# EntradaDigital.net
KiCad netlist of a schematic drawn in Altium Designer
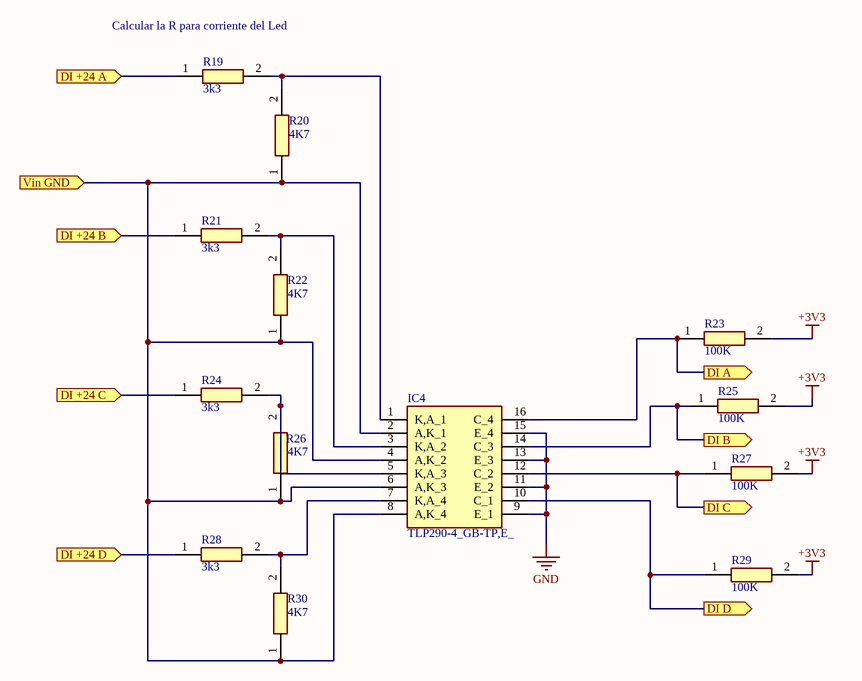
[diagram p0: EntradaDigital.SchDoc]

(export (version "E")
  (design (tool "Eeschema 10.0.6"))
  (components
    (comp (ref "IC4")
      (value "TLP290-4_GB-TP,E_")
      (footprint "SamacSys:SOIC127P700X230-16N")
      (description "Integrated Circuit")
      (fields
        (field (name "MANUFACTURER_PART_NUMBER") "TLP290-4(GB-TP,E)")
        (field (name "MOUSER PART NUMBER") "757-TLP2904GBTPE")
      )
      (libsource (lib "*") (part "TLP290-4_GB-TP,E_"))
    )
    (comp (ref "R19")
      (value "3k3")
      (footprint "SamacSys:RESC3216X75N")
      (description "Resistor")
      (fields
        (field (name "MANUFACTURER_PART_NUMBER") "CR1206-F/-2R00ELF")
        (field (name "MOUSER PART NUMBER") "652-CR1206-F/2R00ELF")
      )
      (libsource (lib "*") (part "CR1206-F_-2R00ELF"))
    )
    (comp (ref "R20")
      (value "4K7")
      (footprint "SamacSys:RESC3216X75N")
      (description "Resistor")
      (fields
        (field (name "MANUFACTURER_PART_NUMBER") "CR1206-F/-2R00ELF")
        (field (name "MOUSER PART NUMBER") "652-CR1206-F/2R00ELF")
      )
      (libsource (lib "") (part "CR1206-F_-2R00ELF_1"))
    )
    (comp (ref "R21")
      (value "3k3")
      (footprint "SamacSys:RESC3216X75N")
      (description "Resistor")
      (fields
        (field (name "MANUFACTURER_PART_NUMBER") "CR1206-F/-2R00ELF")
        (field (name "MOUSER PART NUMBER") "652-CR1206-F/2R00ELF")
      )
      (libsource (lib "*") (part "CR1206-F_-2R00ELF"))
    )
    (comp (ref "R22")
      (value "4K7")
      (footprint "SamacSys:RESC3216X75N")
      (description "Resistor")
      (fields
        (field (name "MANUFACTURER_PART_NUMBER") "CR1206-F/-2R00ELF")
        (field (name "MOUSER PART NUMBER") "652-CR1206-F/2R00ELF")
      )
      (libsource (lib "") (part "CR1206-F_-2R00ELF_1"))
    )
    (comp (ref "R23")
      (value "100K")
      (footprint "SamacSys:RESC3216X75N")
      (description "Resistor")
      (fields
        (field (name "MANUFACTURER_PART_NUMBER") "CR1206-F/-2R00ELF")
        (field (name "MOUSER PART NUMBER") "652-CR1206-F/2R00ELF")
      )
      (libsource (lib "*") (part "CR1206-F_-2R00ELF"))
    )
    (comp (ref "R24")
      (value "3k3")
      (footprint "SamacSys:RESC3216X75N")
      (description "Resistor")
      (fields
        (field (name "MANUFACTURER_PART_NUMBER") "CR1206-F/-2R00ELF")
        (field (name "MOUSER PART NUMBER") "652-CR1206-F/2R00ELF")
      )
      (libsource (lib "*") (part "CR1206-F_-2R00ELF"))
    )
    (comp (ref "R25")
      (value "100K")
      (footprint "SamacSys:RESC3216X75N")
      (description "Resistor")
      (fields
        (field (name "MANUFACTURER_PART_NUMBER") "CR1206-F/-2R00ELF")
        (field (name "MOUSER PART NUMBER") "652-CR1206-F/2R00ELF")
      )
      (libsource (lib "*") (part "CR1206-F_-2R00ELF"))
    )
    (comp (ref "R26")
      (value "4K7")
      (footprint "SamacSys:RESC3216X75N")
      (description "Resistor")
      (fields
        (field (name "MANUFACTURER_PART_NUMBER") "CR1206-F/-2R00ELF")
        (field (name "MOUSER PART NUMBER") "652-CR1206-F/2R00ELF")
      )
      (libsource (lib "") (part "CR1206-F_-2R00ELF_1"))
    )
    (comp (ref "R27")
      (value "100K")
      (footprint "SamacSys:RESC3216X75N")
      (description "Resistor")
      (fields
        (field (name "MANUFACTURER_PART_NUMBER") "CR1206-F/-2R00ELF")
        (field (name "MOUSER PART NUMBER") "652-CR1206-F/2R00ELF")
      )
      (libsource (lib "*") (part "CR1206-F_-2R00ELF"))
    )
    (comp (ref "R28")
      (value "3k3")
      (footprint "SamacSys:RESC3216X75N")
      (description "Resistor")
      (fields
        (field (name "MANUFACTURER_PART_NUMBER") "CR1206-F/-2R00ELF")
        (field (name "MOUSER PART NUMBER") "652-CR1206-F/2R00ELF")
      )
      (libsource (lib "*") (part "CR1206-F_-2R00ELF"))
    )
    (comp (ref "R29")
      (value "100K")
      (footprint "SamacSys:RESC3216X75N")
      (description "Resistor")
      (fields
        (field (name "MANUFACTURER_PART_NUMBER") "CR1206-F/-2R00ELF")
        (field (name "MOUSER PART NUMBER") "652-CR1206-F/2R00ELF")
      )
      (libsource (lib "*") (part "CR1206-F_-2R00ELF"))
    )
    (comp (ref "R30")
      (value "4K7")
      (footprint "SamacSys:RESC3216X75N")
      (description "Resistor")
      (fields
        (field (name "MANUFACTURER_PART_NUMBER") "CR1206-F/-2R00ELF")
        (field (name "MOUSER PART NUMBER") "652-CR1206-F/2R00ELF")
      )
      (libsource (lib "") (part "CR1206-F_-2R00ELF_1"))
    )
  )
  (nets
    (net (code "1") (name "+3V3") (class "Default")
      (node (ref "R23") (pin "2") (pinfunction "2_2") (pintype "passive"))
      (node (ref "R25") (pin "2") (pinfunction "2_2") (pintype "passive"))
      (node (ref "R27") (pin "2") (pinfunction "2_2") (pintype "passive"))
      (node (ref "R29") (pin "2") (pinfunction "2_2") (pintype "passive"))
    )
    (net (code "2") (name "/DI +24 A") (class "Default")
      (node (ref "R19") (pin "1") (pinfunction "1_1") (pintype "passive"))
    )
    (net (code "3") (name "/DI +24 B") (class "Default")
      (node (ref "R21") (pin "1") (pinfunction "1_1") (pintype "passive"))
    )
    (net (code "4") (name "/DI +24 C") (class "Default")
      (node (ref "R24") (pin "1") (pinfunction "1_1") (pintype "passive"))
    )
    (net (code "5") (name "/DI +24 D") (class "Default")
      (node (ref "R28") (pin "1") (pinfunction "1_1") (pintype "passive"))
    )
    (net (code "6") (name "/DI A") (class "Default")
      (node (ref "IC4") (pin "16") (pinfunction "C_4_16") (pintype "passive"))
      (node (ref "R23") (pin "1") (pinfunction "1_1") (pintype "passive"))
    )
    (net (code "7") (name "/DI B") (class "Default")
      (node (ref "IC4") (pin "14") (pinfunction "C_3_14") (pintype "passive"))
      (node (ref "R25") (pin "1") (pinfunction "1_1") (pintype "passive"))
    )
    (net (code "8") (name "/DI C") (class "Default")
      (node (ref "IC4") (pin "12") (pinfunction "C_2_12") (pintype "passive"))
      (node (ref "R27") (pin "1") (pinfunction "1_1") (pintype "passive"))
    )
    (net (code "9") (name "/DI D") (class "Default")
      (node (ref "IC4") (pin "10") (pinfunction "C_1_10") (pintype "passive"))
      (node (ref "R29") (pin "1") (pinfunction "1_1") (pintype "passive"))
    )
    (net (code "10") (name "/Vin GND") (class "Default")
      (node (ref "IC4") (pin "2") (pinfunction "A,K_1_2") (pintype "passive"))
      (node (ref "IC4") (pin "4") (pinfunction "A,K_2_4") (pintype "passive"))
      (node (ref "IC4") (pin "6") (pinfunction "A,K_3_6") (pintype "passive"))
      (node (ref "IC4") (pin "8") (pinfunction "A,K_4_8") (pintype "passive"))
      (node (ref "R20") (pin "1") (pinfunction "1_1") (pintype "passive"))
      (node (ref "R22") (pin "1") (pinfunction "1_1") (pintype "passive"))
      (node (ref "R26") (pin "1") (pinfunction "1_1") (pintype "passive"))
      (node (ref "R30") (pin "1") (pinfunction "1_1") (pintype "passive"))
    )
    (net (code "11") (name "GND") (class "Default")
      (node (ref "IC4") (pin "11") (pinfunction "E_2_11") (pintype "passive"))
      (node (ref "IC4") (pin "13") (pinfunction "E_3_13") (pintype "passive"))
      (node (ref "IC4") (pin "15") (pinfunction "E_4_15") (pintype "passive"))
      (node (ref "IC4") (pin "9") (pinfunction "E_1_9") (pintype "passive"))
    )
    (net (code "12") (name "Net-(IC4-K,A_1)") (class "Default")
      (node (ref "IC4") (pin "1") (pinfunction "K,A_1_1") (pintype "passive"))
      (node (ref "R19") (pin "2") (pinfunction "2_2") (pintype "passive"))
      (node (ref "R20") (pin "2") (pinfunction "2_2") (pintype "passive"))
    )
    (net (code "13") (name "Net-(IC4-K,A_2)") (class "Default")
      (node (ref "IC4") (pin "3") (pinfunction "K,A_2_3") (pintype "passive"))
      (node (ref "R21") (pin "2") (pinfunction "2_2") (pintype "passive"))
      (node (ref "R22") (pin "2") (pinfunction "2_2") (pintype "passive"))
    )
    (net (code "14") (name "Net-(IC4-K,A_3)") (class "Default")
      (node (ref "IC4") (pin "5") (pinfunction "K,A_3_5") (pintype "passive"))
      (node (ref "R24") (pin "2") (pinfunction "2_2") (pintype "passive"))
      (node (ref "R26") (pin "2") (pinfunction "2_2") (pintype "passive"))
    )
    (net (code "15") (name "Net-(IC4-K,A_4)") (class "Default")
      (node (ref "IC4") (pin "7") (pinfunction "K,A_4_7") (pintype "passive"))
      (node (ref "R28") (pin "2") (pinfunction "2_2") (pintype "passive"))
      (node (ref "R30") (pin "2") (pinfunction "2_2") (pintype "passive"))
    )
  )
)
